# DJ_CONTROLLER.net
KiCad netlist of a schematic drawn in EAGLE
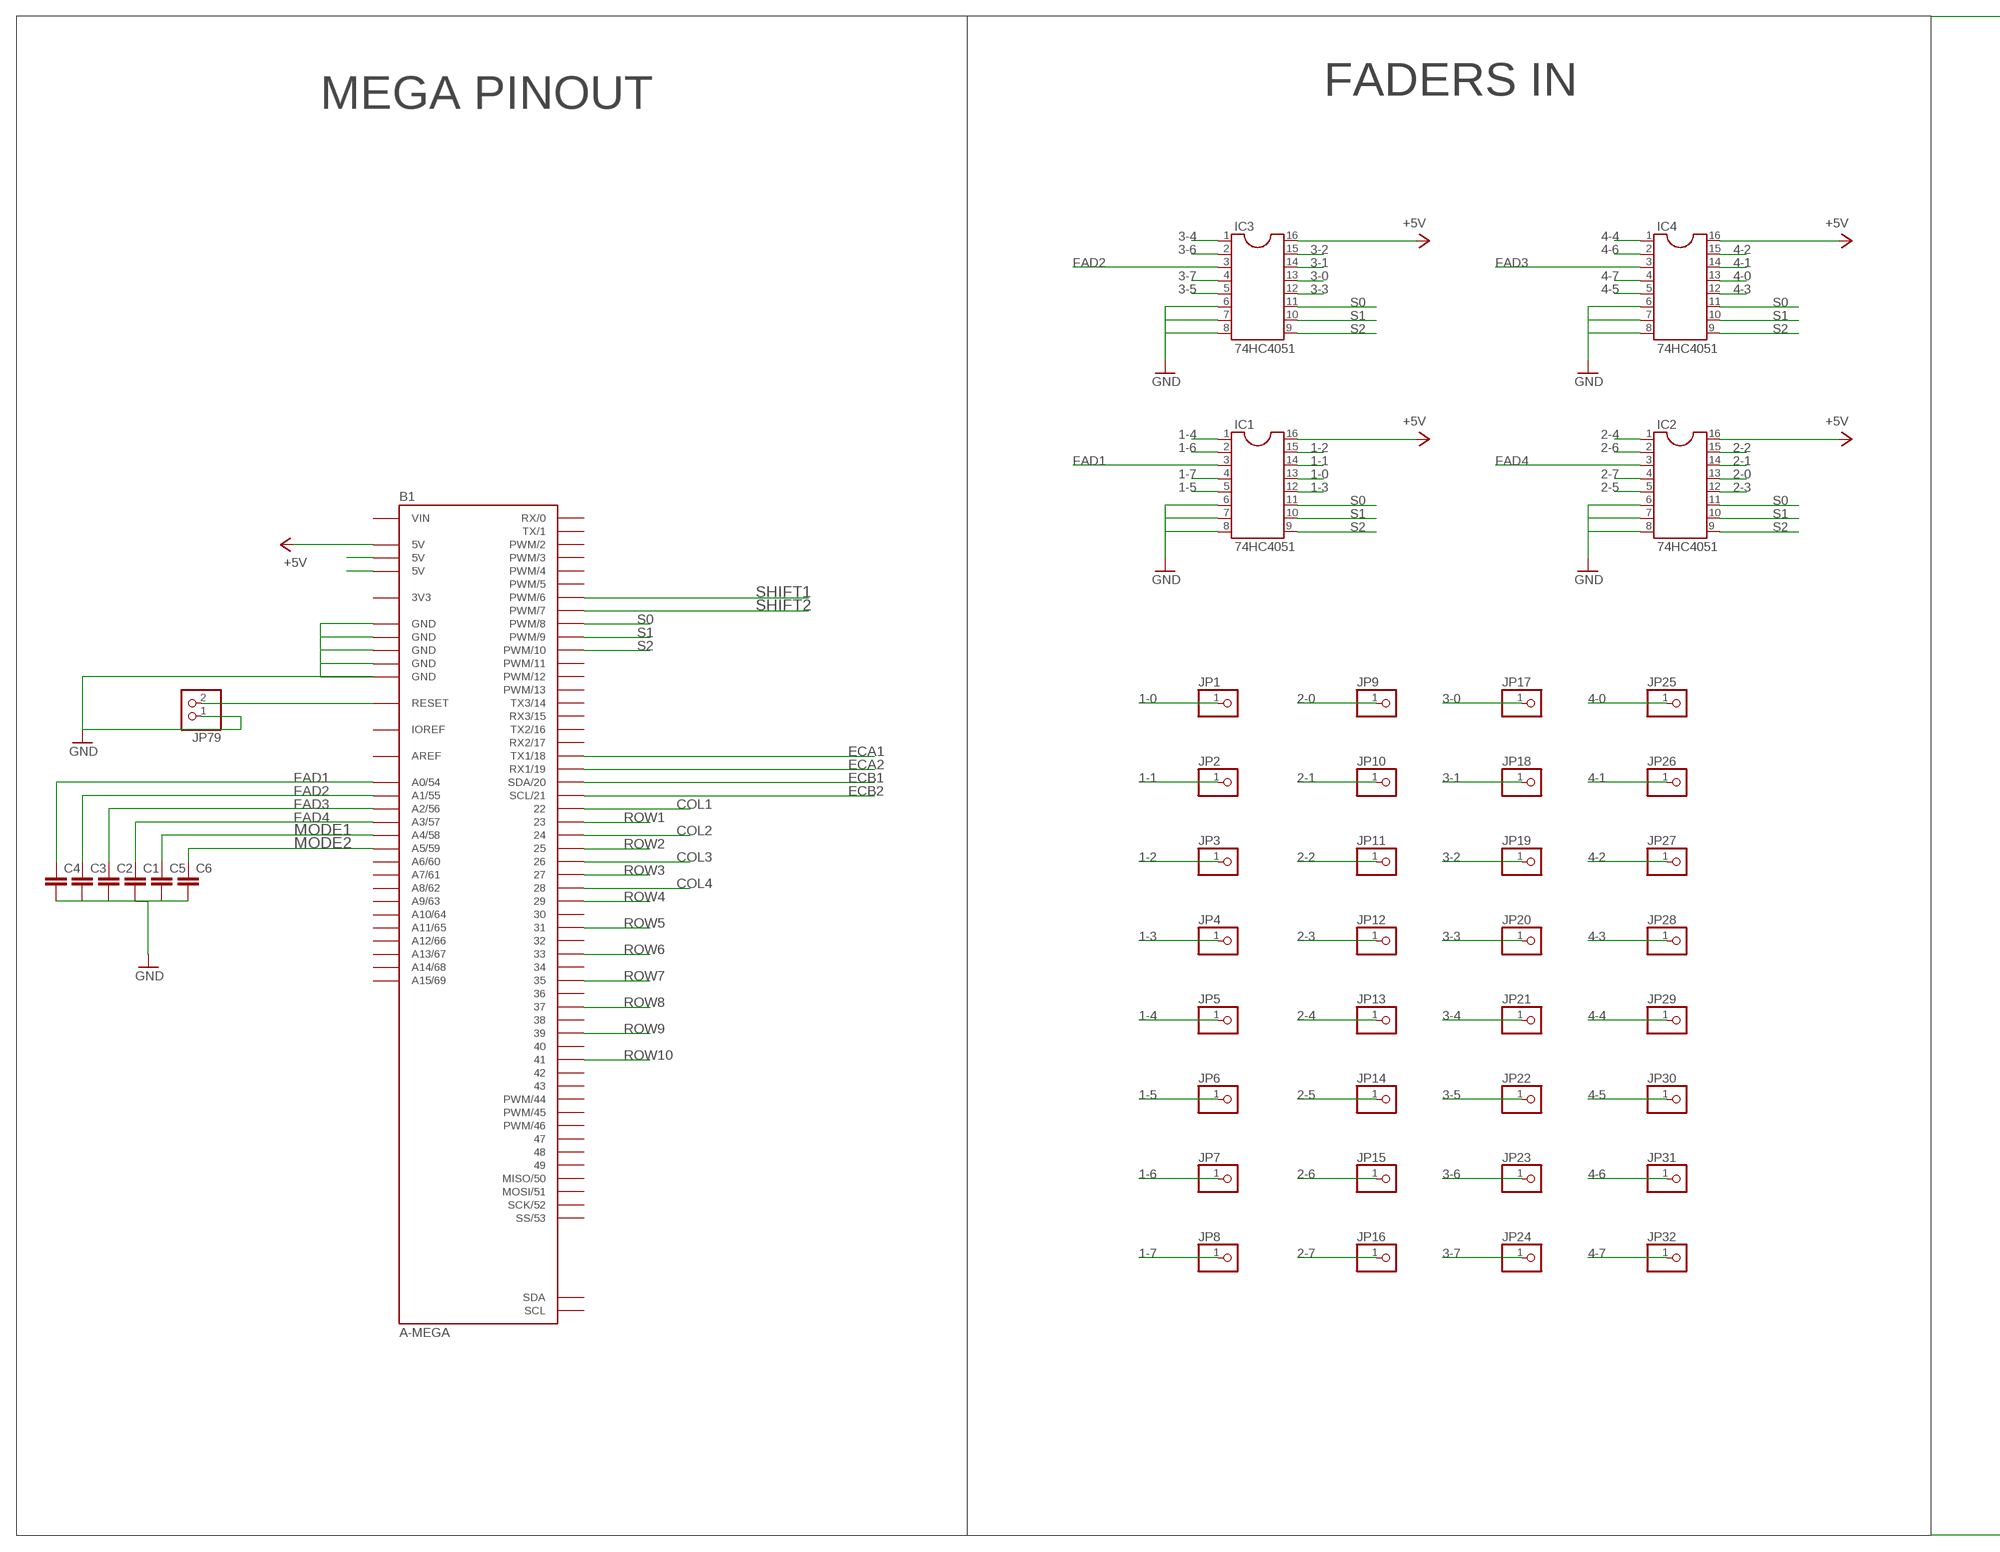
[diagram p0: schematic, sheet 1, part 1 of 2]
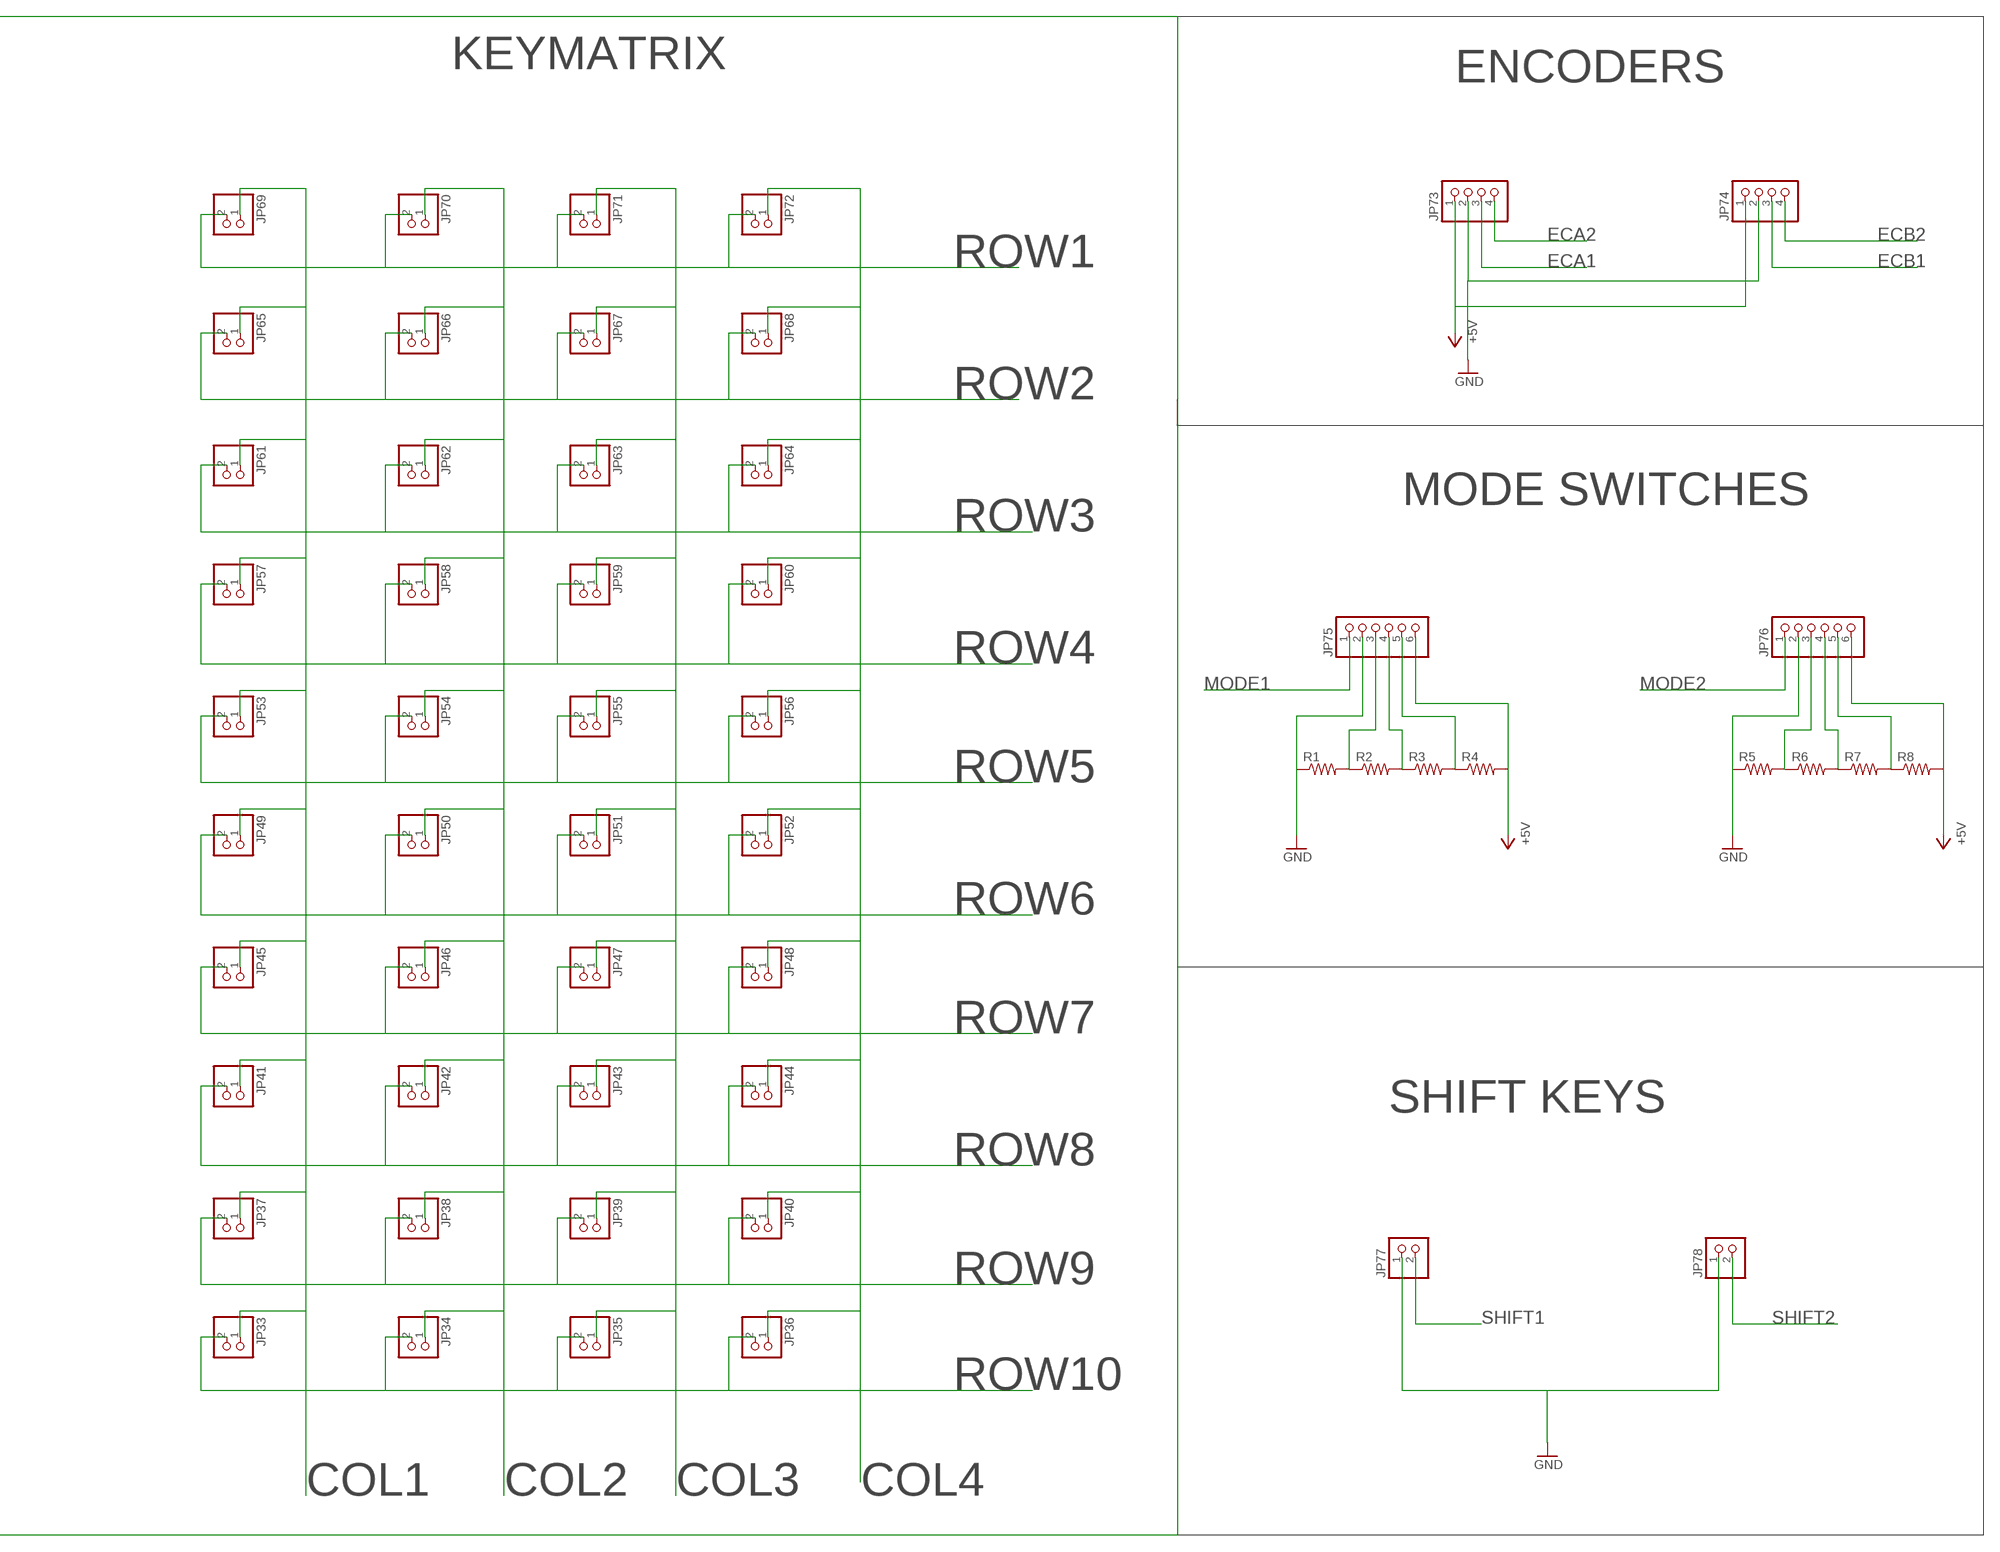
[diagram p1: schematic, sheet 1, part 2 of 2]

(export (version "E")
  (design (tool "Eeschema 10.0.6"))
  (components
    (comp (ref "B1")
      (value "A-MEGA")
      (footprint "eagle-import:A-MEGA")
      (libsource (lib "eagle-import") (part "A-MEGA"))
    )
    (comp (ref "C1")
      (value "C-EU050-025X075")
      (footprint "eagle-import:C050-025X075")
      (libsource (lib "eagle-import") (part "C-EU050-025X075"))
    )
    (comp (ref "C2")
      (value "C-EU050-025X075")
      (footprint "eagle-import:C050-025X075")
      (libsource (lib "eagle-import") (part "C-EU050-025X075"))
    )
    (comp (ref "C3")
      (value "C-EU050-025X075")
      (footprint "eagle-import:C050-025X075")
      (libsource (lib "eagle-import") (part "C-EU050-025X075"))
    )
    (comp (ref "C4")
      (value "C-EU050-025X075")
      (footprint "eagle-import:C050-025X075")
      (libsource (lib "eagle-import") (part "C-EU050-025X075"))
    )
    (comp (ref "C5")
      (value "C-EU050-025X075")
      (footprint "eagle-import:C050-025X075")
      (libsource (lib "eagle-import") (part "C-EU050-025X075"))
    )
    (comp (ref "C6")
      (value "C-EU050-025X075")
      (footprint "eagle-import:C050-025X075")
      (libsource (lib "eagle-import") (part "C-EU050-025X075"))
    )
    (comp (ref "IC1")
      (value "74HC4051")
      (footprint "eagle-import:SOCKET-16")
      (libsource (lib "eagle-import") (part "DIL16S"))
    )
    (comp (ref "IC2")
      (value "74HC4051")
      (footprint "eagle-import:SOCKET-16")
      (libsource (lib "eagle-import") (part "DIL16S"))
    )
    (comp (ref "IC3")
      (value "74HC4051")
      (footprint "eagle-import:SOCKET-16")
      (libsource (lib "eagle-import") (part "DIL16S"))
    )
    (comp (ref "IC4")
      (value "74HC4051")
      (footprint "eagle-import:SOCKET-16")
      (libsource (lib "eagle-import") (part "DIL16S"))
    )
    (comp (ref "JP1")
      (value "PINHD-1X1")
      (footprint "eagle-import:1X01")
      (libsource (lib "eagle-import") (part "PINHD-1X1"))
    )
    (comp (ref "JP2")
      (value "PINHD-1X1")
      (footprint "eagle-import:1X01")
      (libsource (lib "eagle-import") (part "PINHD-1X1"))
    )
    (comp (ref "JP3")
      (value "PINHD-1X1")
      (footprint "eagle-import:1X01")
      (libsource (lib "eagle-import") (part "PINHD-1X1"))
    )
    (comp (ref "JP4")
      (value "PINHD-1X1")
      (footprint "eagle-import:1X01")
      (libsource (lib "eagle-import") (part "PINHD-1X1"))
    )
    (comp (ref "JP5")
      (value "PINHD-1X1")
      (footprint "eagle-import:1X01")
      (libsource (lib "eagle-import") (part "PINHD-1X1"))
    )
    (comp (ref "JP6")
      (value "PINHD-1X1")
      (footprint "eagle-import:1X01")
      (libsource (lib "eagle-import") (part "PINHD-1X1"))
    )
    (comp (ref "JP7")
      (value "PINHD-1X1")
      (footprint "eagle-import:1X01")
      (libsource (lib "eagle-import") (part "PINHD-1X1"))
    )
    (comp (ref "JP8")
      (value "PINHD-1X1")
      (footprint "eagle-import:1X01")
      (libsource (lib "eagle-import") (part "PINHD-1X1"))
    )
    (comp (ref "JP9")
      (value "PINHD-1X1")
      (footprint "eagle-import:1X01")
      (libsource (lib "eagle-import") (part "PINHD-1X1"))
    )
    (comp (ref "JP10")
      (value "PINHD-1X1")
      (footprint "eagle-import:1X01")
      (libsource (lib "eagle-import") (part "PINHD-1X1"))
    )
    (comp (ref "JP11")
      (value "PINHD-1X1")
      (footprint "eagle-import:1X01")
      (libsource (lib "eagle-import") (part "PINHD-1X1"))
    )
    (comp (ref "JP12")
      (value "PINHD-1X1")
      (footprint "eagle-import:1X01")
      (libsource (lib "eagle-import") (part "PINHD-1X1"))
    )
    (comp (ref "JP13")
      (value "PINHD-1X1")
      (footprint "eagle-import:1X01")
      (libsource (lib "eagle-import") (part "PINHD-1X1"))
    )
    (comp (ref "JP14")
      (value "PINHD-1X1")
      (footprint "eagle-import:1X01")
      (libsource (lib "eagle-import") (part "PINHD-1X1"))
    )
    (comp (ref "JP15")
      (value "PINHD-1X1")
      (footprint "eagle-import:1X01")
      (libsource (lib "eagle-import") (part "PINHD-1X1"))
    )
    (comp (ref "JP16")
      (value "PINHD-1X1")
      (footprint "eagle-import:1X01")
      (libsource (lib "eagle-import") (part "PINHD-1X1"))
    )
    (comp (ref "JP17")
      (value "PINHD-1X1")
      (footprint "eagle-import:1X01")
      (libsource (lib "eagle-import") (part "PINHD-1X1"))
    )
    (comp (ref "JP18")
      (value "PINHD-1X1")
      (footprint "eagle-import:1X01")
      (libsource (lib "eagle-import") (part "PINHD-1X1"))
    )
    (comp (ref "JP19")
      (value "PINHD-1X1")
      (footprint "eagle-import:1X01")
      (libsource (lib "eagle-import") (part "PINHD-1X1"))
    )
    (comp (ref "JP20")
      (value "PINHD-1X1")
      (footprint "eagle-import:1X01")
      (libsource (lib "eagle-import") (part "PINHD-1X1"))
    )
    (comp (ref "JP21")
      (value "PINHD-1X1")
      (footprint "eagle-import:1X01")
      (libsource (lib "eagle-import") (part "PINHD-1X1"))
    )
    (comp (ref "JP22")
      (value "PINHD-1X1")
      (footprint "eagle-import:1X01")
      (libsource (lib "eagle-import") (part "PINHD-1X1"))
    )
    (comp (ref "JP23")
      (value "PINHD-1X1")
      (footprint "eagle-import:1X01")
      (libsource (lib "eagle-import") (part "PINHD-1X1"))
    )
    (comp (ref "JP24")
      (value "PINHD-1X1")
      (footprint "eagle-import:1X01")
      (libsource (lib "eagle-import") (part "PINHD-1X1"))
    )
    (comp (ref "JP25")
      (value "PINHD-1X1")
      (footprint "eagle-import:1X01")
      (libsource (lib "eagle-import") (part "PINHD-1X1"))
    )
    (comp (ref "JP26")
      (value "PINHD-1X1")
      (footprint "eagle-import:1X01")
      (libsource (lib "eagle-import") (part "PINHD-1X1"))
    )
    (comp (ref "JP27")
      (value "PINHD-1X1")
      (footprint "eagle-import:1X01")
      (libsource (lib "eagle-import") (part "PINHD-1X1"))
    )
    (comp (ref "JP28")
      (value "PINHD-1X1")
      (footprint "eagle-import:1X01")
      (libsource (lib "eagle-import") (part "PINHD-1X1"))
    )
    (comp (ref "JP29")
      (value "PINHD-1X1")
      (footprint "eagle-import:1X01")
      (libsource (lib "eagle-import") (part "PINHD-1X1"))
    )
    (comp (ref "JP30")
      (value "PINHD-1X1")
      (footprint "eagle-import:1X01")
      (libsource (lib "eagle-import") (part "PINHD-1X1"))
    )
    (comp (ref "JP31")
      (value "PINHD-1X1")
      (footprint "eagle-import:1X01")
      (libsource (lib "eagle-import") (part "PINHD-1X1"))
    )
    (comp (ref "JP32")
      (value "PINHD-1X1")
      (footprint "eagle-import:1X01")
      (libsource (lib "eagle-import") (part "PINHD-1X1"))
    )
    (comp (ref "JP33")
      (value "PINHD-1X2")
      (footprint "eagle-import:1X02")
      (libsource (lib "eagle-import") (part "PINHD-1X2"))
    )
    (comp (ref "JP34")
      (value "PINHD-1X2")
      (footprint "eagle-import:1X02")
      (libsource (lib "eagle-import") (part "PINHD-1X2"))
    )
    (comp (ref "JP35")
      (value "PINHD-1X2")
      (footprint "eagle-import:1X02")
      (libsource (lib "eagle-import") (part "PINHD-1X2"))
    )
    (comp (ref "JP36")
      (value "PINHD-1X2")
      (footprint "eagle-import:1X02")
      (libsource (lib "eagle-import") (part "PINHD-1X2"))
    )
    (comp (ref "JP37")
      (value "PINHD-1X2")
      (footprint "eagle-import:1X02")
      (libsource (lib "eagle-import") (part "PINHD-1X2"))
    )
    (comp (ref "JP38")
      (value "PINHD-1X2")
      (footprint "eagle-import:1X02")
      (libsource (lib "eagle-import") (part "PINHD-1X2"))
    )
    (comp (ref "JP39")
      (value "PINHD-1X2")
      (footprint "eagle-import:1X02")
      (libsource (lib "eagle-import") (part "PINHD-1X2"))
    )
    (comp (ref "JP40")
      (value "PINHD-1X2")
      (footprint "eagle-import:1X02")
      (libsource (lib "eagle-import") (part "PINHD-1X2"))
    )
    (comp (ref "JP41")
      (value "PINHD-1X2")
      (footprint "eagle-import:1X02")
      (libsource (lib "eagle-import") (part "PINHD-1X2"))
    )
    (comp (ref "JP42")
      (value "PINHD-1X2")
      (footprint "eagle-import:1X02")
      (libsource (lib "eagle-import") (part "PINHD-1X2"))
    )
    (comp (ref "JP43")
      (value "PINHD-1X2")
      (footprint "eagle-import:1X02")
      (libsource (lib "eagle-import") (part "PINHD-1X2"))
    )
    (comp (ref "JP44")
      (value "PINHD-1X2")
      (footprint "eagle-import:1X02")
      (libsource (lib "eagle-import") (part "PINHD-1X2"))
    )
    (comp (ref "JP45")
      (value "PINHD-1X2")
      (footprint "eagle-import:1X02")
      (libsource (lib "eagle-import") (part "PINHD-1X2"))
    )
    (comp (ref "JP46")
      (value "PINHD-1X2")
      (footprint "eagle-import:1X02")
      (libsource (lib "eagle-import") (part "PINHD-1X2"))
    )
    (comp (ref "JP47")
      (value "PINHD-1X2")
      (footprint "eagle-import:1X02")
      (libsource (lib "eagle-import") (part "PINHD-1X2"))
    )
    (comp (ref "JP48")
      (value "PINHD-1X2")
      (footprint "eagle-import:1X02")
      (libsource (lib "eagle-import") (part "PINHD-1X2"))
    )
    (comp (ref "JP49")
      (value "PINHD-1X2")
      (footprint "eagle-import:1X02")
      (libsource (lib "eagle-import") (part "PINHD-1X2"))
    )
    (comp (ref "JP50")
      (value "PINHD-1X2")
      (footprint "eagle-import:1X02")
      (libsource (lib "eagle-import") (part "PINHD-1X2"))
    )
    (comp (ref "JP51")
      (value "PINHD-1X2")
      (footprint "eagle-import:1X02")
      (libsource (lib "eagle-import") (part "PINHD-1X2"))
    )
    (comp (ref "JP52")
      (value "PINHD-1X2")
      (footprint "eagle-import:1X02")
      (libsource (lib "eagle-import") (part "PINHD-1X2"))
    )
    (comp (ref "JP53")
      (value "PINHD-1X2")
      (footprint "eagle-import:1X02")
      (libsource (lib "eagle-import") (part "PINHD-1X2"))
    )
    (comp (ref "JP54")
      (value "PINHD-1X2")
      (footprint "eagle-import:1X02")
      (libsource (lib "eagle-import") (part "PINHD-1X2"))
    )
    (comp (ref "JP55")
      (value "PINHD-1X2")
      (footprint "eagle-import:1X02")
      (libsource (lib "eagle-import") (part "PINHD-1X2"))
    )
    (comp (ref "JP56")
      (value "PINHD-1X2")
      (footprint "eagle-import:1X02")
      (libsource (lib "eagle-import") (part "PINHD-1X2"))
    )
    (comp (ref "JP57")
      (value "PINHD-1X2")
      (footprint "eagle-import:1X02")
      (libsource (lib "eagle-import") (part "PINHD-1X2"))
    )
    (comp (ref "JP58")
      (value "PINHD-1X2")
      (footprint "eagle-import:1X02")
      (libsource (lib "eagle-import") (part "PINHD-1X2"))
    )
    (comp (ref "JP59")
      (value "PINHD-1X2")
      (footprint "eagle-import:1X02")
      (libsource (lib "eagle-import") (part "PINHD-1X2"))
    )
    (comp (ref "JP60")
      (value "PINHD-1X2")
      (footprint "eagle-import:1X02")
      (libsource (lib "eagle-import") (part "PINHD-1X2"))
    )
    (comp (ref "JP61")
      (value "PINHD-1X2")
      (footprint "eagle-import:1X02")
      (libsource (lib "eagle-import") (part "PINHD-1X2"))
    )
    (comp (ref "JP62")
      (value "PINHD-1X2")
      (footprint "eagle-import:1X02")
      (libsource (lib "eagle-import") (part "PINHD-1X2"))
    )
    (comp (ref "JP63")
      (value "PINHD-1X2")
      (footprint "eagle-import:1X02")
      (libsource (lib "eagle-import") (part "PINHD-1X2"))
    )
    (comp (ref "JP64")
      (value "PINHD-1X2")
      (footprint "eagle-import:1X02")
      (libsource (lib "eagle-import") (part "PINHD-1X2"))
    )
    (comp (ref "JP65")
      (value "PINHD-1X2")
      (footprint "eagle-import:1X02")
      (libsource (lib "eagle-import") (part "PINHD-1X2"))
    )
    (comp (ref "JP66")
      (value "PINHD-1X2")
      (footprint "eagle-import:1X02")
      (libsource (lib "eagle-import") (part "PINHD-1X2"))
    )
    (comp (ref "JP67")
      (value "PINHD-1X2")
      (footprint "eagle-import:1X02")
      (libsource (lib "eagle-import") (part "PINHD-1X2"))
    )
    (comp (ref "JP68")
      (value "PINHD-1X2")
      (footprint "eagle-import:1X02")
      (libsource (lib "eagle-import") (part "PINHD-1X2"))
    )
    (comp (ref "JP69")
      (value "PINHD-1X2")
      (footprint "eagle-import:1X02")
      (libsource (lib "eagle-import") (part "PINHD-1X2"))
    )
    (comp (ref "JP70")
      (value "PINHD-1X2")
      (footprint "eagle-import:1X02")
      (libsource (lib "eagle-import") (part "PINHD-1X2"))
    )
    (comp (ref "JP71")
      (value "PINHD-1X2")
      (footprint "eagle-import:1X02")
      (libsource (lib "eagle-import") (part "PINHD-1X2"))
    )
    (comp (ref "JP72")
      (value "PINHD-1X2")
      (footprint "eagle-import:1X02")
      (libsource (lib "eagle-import") (part "PINHD-1X2"))
    )
    (comp (ref "JP73")
      (value "PINHD-1X4")
      (footprint "eagle-import:1X04")
      (libsource (lib "eagle-import") (part "PINHD-1X4"))
    )
    (comp (ref "JP74")
      (value "PINHD-1X4")
      (footprint "eagle-import:1X04")
      (libsource (lib "eagle-import") (part "PINHD-1X4"))
    )
    (comp (ref "JP75")
      (value "PINHD-1X6")
      (footprint "eagle-import:1X06")
      (libsource (lib "eagle-import") (part "PINHD-1X6"))
    )
    (comp (ref "JP76")
      (value "PINHD-1X6")
      (footprint "eagle-import:1X06")
      (libsource (lib "eagle-import") (part "PINHD-1X6"))
    )
    (comp (ref "JP77")
      (value "PINHD-1X2")
      (footprint "eagle-import:1X02")
      (libsource (lib "eagle-import") (part "PINHD-1X2"))
    )
    (comp (ref "JP78")
      (value "PINHD-1X2")
      (footprint "eagle-import:1X02")
      (libsource (lib "eagle-import") (part "PINHD-1X2"))
    )
    (comp (ref "JP79")
      (value "PINHD-1X2")
      (footprint "eagle-import:1X02")
      (libsource (lib "eagle-import") (part "PINHD-1X2"))
    )
    (comp (ref "R1")
      (value "R-US_0204/7")
      (footprint "eagle-import:0204_7")
      (libsource (lib "eagle-import") (part "R-US_0204/7"))
    )
    (comp (ref "R2")
      (value "R-US_0204/7")
      (footprint "eagle-import:0204_7")
      (libsource (lib "eagle-import") (part "R-US_0204/7"))
    )
    (comp (ref "R3")
      (value "R-US_0204/7")
      (footprint "eagle-import:0204_7")
      (libsource (lib "eagle-import") (part "R-US_0204/7"))
    )
    (comp (ref "R4")
      (value "R-US_0204/7")
      (footprint "eagle-import:0204_7")
      (libsource (lib "eagle-import") (part "R-US_0204/7"))
    )
    (comp (ref "R5")
      (value "R-US_0204/7")
      (footprint "eagle-import:0204_7")
      (libsource (lib "eagle-import") (part "R-US_0204/7"))
    )
    (comp (ref "R6")
      (value "R-US_0204/7")
      (footprint "eagle-import:0204_7")
      (libsource (lib "eagle-import") (part "R-US_0204/7"))
    )
    (comp (ref "R7")
      (value "R-US_0204/7")
      (footprint "eagle-import:0204_7")
      (libsource (lib "eagle-import") (part "R-US_0204/7"))
    )
    (comp (ref "R8")
      (value "R-US_0204/7")
      (footprint "eagle-import:0204_7")
      (libsource (lib "eagle-import") (part "R-US_0204/7"))
    )
  )
  (nets
    (net (code "1") (name "+5V") (class "Default")
      (node (ref "B1") (pin "5V@1") (pinfunction "5V_5V@1") (pintype "power_in"))
      (node (ref "IC1") (pin "16") (pinfunction "16_16") (pintype "passive"))
      (node (ref "IC2") (pin "16") (pinfunction "16_16") (pintype "passive"))
      (node (ref "IC3") (pin "16") (pinfunction "16_16") (pintype "passive"))
      (node (ref "IC4") (pin "16") (pinfunction "16_16") (pintype "passive"))
      (node (ref "JP73") (pin "1") (pinfunction "1_1") (pintype "passive"))
      (node (ref "JP74") (pin "1") (pinfunction "1_1") (pintype "passive"))
      (node (ref "JP75") (pin "6") (pinfunction "6_6") (pintype "passive"))
      (node (ref "JP76") (pin "6") (pinfunction "6_6") (pintype "passive"))
      (node (ref "R4") (pin "2") (pinfunction "2_2") (pintype "passive"))
      (node (ref "R8") (pin "2") (pinfunction "2_2") (pintype "passive"))
    )
    (net (code "2") (name "/1-0") (class "Default")
      (node (ref "IC1") (pin "13") (pinfunction "13_13") (pintype "passive"))
      (node (ref "JP1") (pin "1") (pinfunction "1_1") (pintype "passive"))
    )
    (net (code "3") (name "/1-1") (class "Default")
      (node (ref "IC1") (pin "14") (pinfunction "14_14") (pintype "passive"))
      (node (ref "JP2") (pin "1") (pinfunction "1_1") (pintype "passive"))
    )
    (net (code "4") (name "/1-2") (class "Default")
      (node (ref "IC1") (pin "15") (pinfunction "15_15") (pintype "passive"))
      (node (ref "JP3") (pin "1") (pinfunction "1_1") (pintype "passive"))
    )
    (net (code "5") (name "/1-3") (class "Default")
      (node (ref "IC1") (pin "12") (pinfunction "12_12") (pintype "passive"))
      (node (ref "JP4") (pin "1") (pinfunction "1_1") (pintype "passive"))
    )
    (net (code "6") (name "/1-4") (class "Default")
      (node (ref "IC1") (pin "1") (pinfunction "1_1") (pintype "passive"))
      (node (ref "JP5") (pin "1") (pinfunction "1_1") (pintype "passive"))
    )
    (net (code "7") (name "/1-5") (class "Default")
      (node (ref "IC1") (pin "5") (pinfunction "5_5") (pintype "passive"))
      (node (ref "JP6") (pin "1") (pinfunction "1_1") (pintype "passive"))
    )
    (net (code "8") (name "/1-6") (class "Default")
      (node (ref "IC1") (pin "2") (pinfunction "2_2") (pintype "passive"))
      (node (ref "JP7") (pin "1") (pinfunction "1_1") (pintype "passive"))
    )
    (net (code "9") (name "/1-7") (class "Default")
      (node (ref "IC1") (pin "4") (pinfunction "4_4") (pintype "passive"))
      (node (ref "JP8") (pin "1") (pinfunction "1_1") (pintype "passive"))
    )
    (net (code "10") (name "/2-0") (class "Default")
      (node (ref "IC2") (pin "13") (pinfunction "13_13") (pintype "passive"))
      (node (ref "JP9") (pin "1") (pinfunction "1_1") (pintype "passive"))
    )
    (net (code "11") (name "/2-1") (class "Default")
      (node (ref "IC2") (pin "14") (pinfunction "14_14") (pintype "passive"))
      (node (ref "JP10") (pin "1") (pinfunction "1_1") (pintype "passive"))
    )
    (net (code "12") (name "/2-2") (class "Default")
      (node (ref "IC2") (pin "15") (pinfunction "15_15") (pintype "passive"))
      (node (ref "JP11") (pin "1") (pinfunction "1_1") (pintype "passive"))
    )
    (net (code "13") (name "/2-3") (class "Default")
      (node (ref "IC2") (pin "12") (pinfunction "12_12") (pintype "passive"))
      (node (ref "JP12") (pin "1") (pinfunction "1_1") (pintype "passive"))
    )
    (net (code "14") (name "/2-4") (class "Default")
      (node (ref "IC2") (pin "1") (pinfunction "1_1") (pintype "passive"))
      (node (ref "JP13") (pin "1") (pinfunction "1_1") (pintype "passive"))
    )
    (net (code "15") (name "/2-5") (class "Default")
      (node (ref "IC2") (pin "5") (pinfunction "5_5") (pintype "passive"))
      (node (ref "JP14") (pin "1") (pinfunction "1_1") (pintype "passive"))
    )
    (net (code "16") (name "/2-6") (class "Default")
      (node (ref "IC2") (pin "2") (pinfunction "2_2") (pintype "passive"))
      (node (ref "JP15") (pin "1") (pinfunction "1_1") (pintype "passive"))
    )
    (net (code "17") (name "/2-7") (class "Default")
      (node (ref "IC2") (pin "4") (pinfunction "4_4") (pintype "passive"))
      (node (ref "JP16") (pin "1") (pinfunction "1_1") (pintype "passive"))
    )
    (net (code "18") (name "/3-0") (class "Default")
      (node (ref "IC3") (pin "13") (pinfunction "13_13") (pintype "passive"))
      (node (ref "JP17") (pin "1") (pinfunction "1_1") (pintype "passive"))
    )
    (net (code "19") (name "/3-1") (class "Default")
      (node (ref "IC3") (pin "14") (pinfunction "14_14") (pintype "passive"))
      (node (ref "JP18") (pin "1") (pinfunction "1_1") (pintype "passive"))
    )
    (net (code "20") (name "/3-2") (class "Default")
      (node (ref "IC3") (pin "15") (pinfunction "15_15") (pintype "passive"))
      (node (ref "JP19") (pin "1") (pinfunction "1_1") (pintype "passive"))
    )
    (net (code "21") (name "/3-3") (class "Default")
      (node (ref "IC3") (pin "12") (pinfunction "12_12") (pintype "passive"))
      (node (ref "JP20") (pin "1") (pinfunction "1_1") (pintype "passive"))
    )
    (net (code "22") (name "/3-4") (class "Default")
      (node (ref "IC3") (pin "1") (pinfunction "1_1") (pintype "passive"))
      (node (ref "JP21") (pin "1") (pinfunction "1_1") (pintype "passive"))
    )
    (net (code "23") (name "/3-5") (class "Default")
      (node (ref "IC3") (pin "5") (pinfunction "5_5") (pintype "passive"))
      (node (ref "JP22") (pin "1") (pinfunction "1_1") (pintype "passive"))
    )
    (net (code "24") (name "/3-6") (class "Default")
      (node (ref "IC3") (pin "2") (pinfunction "2_2") (pintype "passive"))
      (node (ref "JP23") (pin "1") (pinfunction "1_1") (pintype "passive"))
    )
    (net (code "25") (name "/3-7") (class "Default")
      (node (ref "IC3") (pin "4") (pinfunction "4_4") (pintype "passive"))
      (node (ref "JP24") (pin "1") (pinfunction "1_1") (pintype "passive"))
    )
    (net (code "26") (name "/3V3") (class "Default")
      (node (ref "B1") (pin "3V3") (pinfunction "3V3_3V3") (pintype "power_in"))
    )
    (net (code "27") (name "/4-0") (class "Default")
      (node (ref "IC4") (pin "13") (pinfunction "13_13") (pintype "passive"))
      (node (ref "JP25") (pin "1") (pinfunction "1_1") (pintype "passive"))
    )
    (net (code "28") (name "/4-1") (class "Default")
      (node (ref "IC4") (pin "14") (pinfunction "14_14") (pintype "passive"))
      (node (ref "JP26") (pin "1") (pinfunction "1_1") (pintype "passive"))
    )
    (net (code "29") (name "/4-2") (class "Default")
      (node (ref "IC4") (pin "15") (pinfunction "15_15") (pintype "passive"))
      (node (ref "JP27") (pin "1") (pinfunction "1_1") (pintype "passive"))
    )
    (net (code "30") (name "/4-3") (class "Default")
      (node (ref "IC4") (pin "12") (pinfunction "12_12") (pintype "passive"))
      (node (ref "JP28") (pin "1") (pinfunction "1_1") (pintype "passive"))
    )
    (net (code "31") (name "/4-4") (class "Default")
      (node (ref "IC4") (pin "1") (pinfunction "1_1") (pintype "passive"))
      (node (ref "JP29") (pin "1") (pinfunction "1_1") (pintype "passive"))
    )
    (net (code "32") (name "/4-5") (class "Default")
      (node (ref "IC4") (pin "5") (pinfunction "5_5") (pintype "passive"))
      (node (ref "JP30") (pin "1") (pinfunction "1_1") (pintype "passive"))
    )
    (net (code "33") (name "/4-6") (class "Default")
      (node (ref "IC4") (pin "2") (pinfunction "2_2") (pintype "passive"))
      (node (ref "JP31") (pin "1") (pinfunction "1_1") (pintype "passive"))
    )
    (net (code "34") (name "/4-7") (class "Default")
      (node (ref "IC4") (pin "4") (pinfunction "4_4") (pintype "passive"))
      (node (ref "JP32") (pin "1") (pinfunction "1_1") (pintype "passive"))
    )
    (net (code "35") (name "/AREF") (class "Default")
      (node (ref "B1") (pin "AREF") (pinfunction "AREF_AREF") (pintype "power_in"))
    )
    (net (code "36") (name "/COL1") (class "Default")
      (node (ref "B1") (pin "22") (pinfunction "22_22") (pintype "bidirectional"))
      (node (ref "JP33") (pin "1") (pinfunction "1_1") (pintype "passive"))
      (node (ref "JP37") (pin "1") (pinfunction "1_1") (pintype "passive"))
      (node (ref "JP41") (pin "1") (pinfunction "1_1") (pintype "passive"))
      (node (ref "JP45") (pin "1") (pinfunction "1_1") (pintype "passive"))
      (node (ref "JP49") (pin "1") (pinfunction "1_1") (pintype "passive"))
      (node (ref "JP53") (pin "1") (pinfunction "1_1") (pintype "passive"))
      (node (ref "JP57") (pin "1") (pinfunction "1_1") (pintype "passive"))
      (node (ref "JP61") (pin "1") (pinfunction "1_1") (pintype "passive"))
      (node (ref "JP65") (pin "1") (pinfunction "1_1") (pintype "passive"))
      (node (ref "JP69") (pin "1") (pinfunction "1_1") (pintype "passive"))
    )
    (net (code "37") (name "/COL2") (class "Default")
      (node (ref "B1") (pin "24") (pinfunction "24_24") (pintype "bidirectional"))
      (node (ref "JP34") (pin "1") (pinfunction "1_1") (pintype "passive"))
      (node (ref "JP38") (pin "1") (pinfunction "1_1") (pintype "passive"))
      (node (ref "JP42") (pin "1") (pinfunction "1_1") (pintype "passive"))
      (node (ref "JP46") (pin "1") (pinfunction "1_1") (pintype "passive"))
      (node (ref "JP50") (pin "1") (pinfunction "1_1") (pintype "passive"))
      (node (ref "JP54") (pin "1") (pinfunction "1_1") (pintype "passive"))
      (node (ref "JP58") (pin "1") (pinfunction "1_1") (pintype "passive"))
      (node (ref "JP62") (pin "1") (pinfunction "1_1") (pintype "passive"))
      (node (ref "JP66") (pin "1") (pinfunction "1_1") (pintype "passive"))
      (node (ref "JP70") (pin "1") (pinfunction "1_1") (pintype "passive"))
    )
    (net (code "38") (name "/COL3") (class "Default")
      (node (ref "B1") (pin "26") (pinfunction "26_26") (pintype "bidirectional"))
      (node (ref "JP35") (pin "1") (pinfunction "1_1") (pintype "passive"))
      (node (ref "JP39") (pin "1") (pinfunction "1_1") (pintype "passive"))
      (node (ref "JP43") (pin "1") (pinfunction "1_1") (pintype "passive"))
      (node (ref "JP47") (pin "1") (pinfunction "1_1") (pintype "passive"))
      (node (ref "JP51") (pin "1") (pinfunction "1_1") (pintype "passive"))
      (node (ref "JP55") (pin "1") (pinfunction "1_1") (pintype "passive"))
      (node (ref "JP59") (pin "1") (pinfunction "1_1") (pintype "passive"))
      (node (ref "JP63") (pin "1") (pinfunction "1_1") (pintype "passive"))
      (node (ref "JP67") (pin "1") (pinfunction "1_1") (pintype "passive"))
      (node (ref "JP71") (pin "1") (pinfunction "1_1") (pintype "passive"))
    )
    (net (code "39") (name "/COL4") (class "Default")
      (node (ref "B1") (pin "28") (pinfunction "28_28") (pintype "bidirectional"))
      (node (ref "JP36") (pin "1") (pinfunction "1_1") (pintype "passive"))
      (node (ref "JP40") (pin "1") (pinfunction "1_1") (pintype "passive"))
      (node (ref "JP44") (pin "1") (pinfunction "1_1") (pintype "passive"))
      (node (ref "JP48") (pin "1") (pinfunction "1_1") (pintype "passive"))
      (node (ref "JP52") (pin "1") (pinfunction "1_1") (pintype "passive"))
      (node (ref "JP56") (pin "1") (pinfunction "1_1") (pintype "passive"))
      (node (ref "JP60") (pin "1") (pinfunction "1_1") (pintype "passive"))
      (node (ref "JP64") (pin "1") (pinfunction "1_1") (pintype "passive"))
      (node (ref "JP68") (pin "1") (pinfunction "1_1") (pintype "passive"))
      (node (ref "JP72") (pin "1") (pinfunction "1_1") (pintype "passive"))
    )
    (net (code "40") (name "/ECA1") (class "Default")
      (node (ref "B1") (pin "18") (pinfunction "TX1/18_18") (pintype "bidirectional"))
      (node (ref "JP73") (pin "3") (pinfunction "3_3") (pintype "passive"))
    )
    (net (code "41") (name "/ECA2") (class "Default")
      (node (ref "B1") (pin "19") (pinfunction "RX1/19_19") (pintype "bidirectional"))
      (node (ref "JP73") (pin "4") (pinfunction "4_4") (pintype "passive"))
    )
    (net (code "42") (name "/ECB1") (class "Default")
      (node (ref "B1") (pin "20") (pinfunction "SDA/20_20") (pintype "bidirectional"))
      (node (ref "JP74") (pin "3") (pinfunction "3_3") (pintype "passive"))
    )
    (net (code "43") (name "/ECB2") (class "Default")
      (node (ref "B1") (pin "21") (pinfunction "SCL/21_21") (pintype "bidirectional"))
      (node (ref "JP74") (pin "4") (pinfunction "4_4") (pintype "passive"))
    )
    (net (code "44") (name "/FAD1") (class "Default")
      (node (ref "B1") (pin "A0") (pinfunction "A0/54_A0") (pintype "bidirectional"))
      (node (ref "C4") (pin "1") (pinfunction "1_1") (pintype "passive"))
      (node (ref "IC1") (pin "3") (pinfunction "3_3") (pintype "passive"))
    )
    (net (code "45") (name "/FAD2") (class "Default")
      (node (ref "B1") (pin "A1") (pinfunction "A1/55_A1") (pintype "bidirectional"))
      (node (ref "C3") (pin "1") (pinfunction "1_1") (pintype "passive"))
      (node (ref "IC3") (pin "3") (pinfunction "3_3") (pintype "passive"))
    )
    (net (code "46") (name "/FAD3") (class "Default")
      (node (ref "B1") (pin "A2") (pinfunction "A2/56_A2") (pintype "bidirectional"))
      (node (ref "C2") (pin "1") (pinfunction "1_1") (pintype "passive"))
      (node (ref "IC4") (pin "3") (pinfunction "3_3") (pintype "passive"))
    )
    (net (code "47") (name "/FAD4") (class "Default")
      (node (ref "B1") (pin "A3") (pinfunction "A3/57_A3") (pintype "bidirectional"))
      (node (ref "C1") (pin "1") (pinfunction "1_1") (pintype "passive"))
      (node (ref "IC2") (pin "3") (pinfunction "3_3") (pintype "passive"))
    )
    (net (code "48") (name "/IOREF") (class "Default")
      (node (ref "B1") (pin "IOREF") (pinfunction "IOREF_IOREF") (pintype "power_in"))
    )
    (net (code "49") (name "/MODE1") (class "Default")
      (node (ref "B1") (pin "A4") (pinfunction "A4/58_A4") (pintype "bidirectional"))
      (node (ref "C5") (pin "1") (pinfunction "1_1") (pintype "passive"))
      (node (ref "JP75") (pin "1") (pinfunction "1_1") (pintype "passive"))
    )
    (net (code "50") (name "/MODE2") (class "Default")
      (node (ref "B1") (pin "A5") (pinfunction "A5/59_A5") (pintype "bidirectional"))
      (node (ref "C6") (pin "1") (pinfunction "1_1") (pintype "passive"))
      (node (ref "JP76") (pin "1") (pinfunction "1_1") (pintype "passive"))
    )
    (net (code "51") (name "/ROW1") (class "Default")
      (node (ref "B1") (pin "23") (pinfunction "23_23") (pintype "bidirectional"))
      (node (ref "JP69") (pin "2") (pinfunction "2_2") (pintype "passive"))
      (node (ref "JP70") (pin "2") (pinfunction "2_2") (pintype "passive"))
      (node (ref "JP71") (pin "2") (pinfunction "2_2") (pintype "passive"))
      (node (ref "JP72") (pin "2") (pinfunction "2_2") (pintype "passive"))
    )
    (net (code "52") (name "/ROW2") (class "Default")
      (node (ref "B1") (pin "25") (pinfunction "25_25") (pintype "bidirectional"))
      (node (ref "JP65") (pin "2") (pinfunction "2_2") (pintype "passive"))
      (node (ref "JP66") (pin "2") (pinfunction "2_2") (pintype "passive"))
      (node (ref "JP67") (pin "2") (pinfunction "2_2") (pintype "passive"))
      (node (ref "JP68") (pin "2") (pinfunction "2_2") (pintype "passive"))
    )
    (net (code "53") (name "/ROW3") (class "Default")
      (node (ref "B1") (pin "27") (pinfunction "27_27") (pintype "bidirectional"))
      (node (ref "JP61") (pin "2") (pinfunction "2_2") (pintype "passive"))
      (node (ref "JP62") (pin "2") (pinfunction "2_2") (pintype "passive"))
      (node (ref "JP63") (pin "2") (pinfunction "2_2") (pintype "passive"))
      (node (ref "JP64") (pin "2") (pinfunction "2_2") (pintype "passive"))
    )
    (net (code "54") (name "/ROW4") (class "Default")
      (node (ref "B1") (pin "29") (pinfunction "29_29") (pintype "bidirectional"))
      (node (ref "JP57") (pin "2") (pinfunction "2_2") (pintype "passive"))
      (node (ref "JP58") (pin "2") (pinfunction "2_2") (pintype "passive"))
      (node (ref "JP59") (pin "2") (pinfunction "2_2") (pintype "passive"))
      (node (ref "JP60") (pin "2") (pinfunction "2_2") (pintype "passive"))
    )
    (net (code "55") (name "/ROW5") (class "Default")
      (node (ref "B1") (pin "31") (pinfunction "31_31") (pintype "bidirectional"))
      (node (ref "JP53") (pin "2") (pinfunction "2_2") (pintype "passive"))
      (node (ref "JP54") (pin "2") (pinfunction "2_2") (pintype "passive"))
      (node (ref "JP55") (pin "2") (pinfunction "2_2") (pintype "passive"))
      (node (ref "JP56") (pin "2") (pinfunction "2_2") (pintype "passive"))
    )
    (net (code "56") (name "/ROW6") (class "Default")
      (node (ref "B1") (pin "33") (pinfunction "33_33") (pintype "bidirectional"))
      (node (ref "JP49") (pin "2") (pinfunction "2_2") (pintype "passive"))
      (node (ref "JP50") (pin "2") (pinfunction "2_2") (pintype "passive"))
      (node (ref "JP51") (pin "2") (pinfunction "2_2") (pintype "passive"))
      (node (ref "JP52") (pin "2") (pinfunction "2_2") (pintype "passive"))
    )
    (net (code "57") (name "/ROW7") (class "Default")
      (node (ref "B1") (pin "35") (pinfunction "35_35") (pintype "bidirectional"))
      (node (ref "JP45") (pin "2") (pinfunction "2_2") (pintype "passive"))
      (node (ref "JP46") (pin "2") (pinfunction "2_2") (pintype "passive"))
      (node (ref "JP47") (pin "2") (pinfunction "2_2") (pintype "passive"))
      (node (ref "JP48") (pin "2") (pinfunction "2_2") (pintype "passive"))
    )
    (net (code "58") (name "/ROW8") (class "Default")
      (node (ref "B1") (pin "37") (pinfunction "37_37") (pintype "bidirectional"))
      (node (ref "JP41") (pin "2") (pinfunction "2_2") (pintype "passive"))
      (node (ref "JP42") (pin "2") (pinfunction "2_2") (pintype "passive"))
      (node (ref "JP43") (pin "2") (pinfunction "2_2") (pintype "passive"))
      (node (ref "JP44") (pin "2") (pinfunction "2_2") (pintype "passive"))
    )
    (net (code "59") (name "/ROW9") (class "Default")
      (node (ref "B1") (pin "39") (pinfunction "39_39") (pintype "bidirectional"))
      (node (ref "JP37") (pin "2") (pinfunction "2_2") (pintype "passive"))
      (node (ref "JP38") (pin "2") (pinfunction "2_2") (pintype "passive"))
      (node (ref "JP39") (pin "2") (pinfunction "2_2") (pintype "passive"))
      (node (ref "JP40") (pin "2") (pinfunction "2_2") (pintype "passive"))
    )
    (net (code "60") (name "/ROW10") (class "Default")
      (node (ref "B1") (pin "41") (pinfunction "41_41") (pintype "bidirectional"))
      (node (ref "JP33") (pin "2") (pinfunction "2_2") (pintype "passive"))
      (node (ref "JP34") (pin "2") (pinfunction "2_2") (pintype "passive"))
      (node (ref "JP35") (pin "2") (pinfunction "2_2") (pintype "passive"))
      (node (ref "JP36") (pin "2") (pinfunction "2_2") (pintype "passive"))
    )
    (net (code "61") (name "/S0") (class "Default")
      (node (ref "B1") (pin "8") (pinfunction "PWM/8_8") (pintype "bidirectional"))
      (node (ref "IC1") (pin "11") (pinfunction "11_11") (pintype "passive"))
      (node (ref "IC2") (pin "11") (pinfunction "11_11") (pintype "passive"))
      (node (ref "IC3") (pin "11") (pinfunction "11_11") (pintype "passive"))
      (node (ref "IC4") (pin "11") (pinfunction "11_11") (pintype "passive"))
    )
    (net (code "62") (name "/S1") (class "Default")
      (node (ref "B1") (pin "9") (pinfunction "PWM/9_9") (pintype "bidirectional"))
      (node (ref "IC1") (pin "10") (pinfunction "10_10") (pintype "passive"))
      (node (ref "IC2") (pin "10") (pinfunction "10_10") (pintype "passive"))
      (node (ref "IC3") (pin "10") (pinfunction "10_10") (pintype "passive"))
      (node (ref "IC4") (pin "10") (pinfunction "10_10") (pintype "passive"))
    )
    (net (code "63") (name "/S2") (class "Default")
      (node (ref "B1") (pin "10") (pinfunction "PWM/10_10") (pintype "bidirectional"))
      (node (ref "IC1") (pin "9") (pinfunction "9_9") (pintype "passive"))
      (node (ref "IC2") (pin "9") (pinfunction "9_9") (pintype "passive"))
      (node (ref "IC3") (pin "9") (pinfunction "9_9") (pintype "passive"))
      (node (ref "IC4") (pin "9") (pinfunction "9_9") (pintype "passive"))
    )
    (net (code "64") (name "/SHIFT1") (class "Default")
      (node (ref "B1") (pin "6") (pinfunction "PWM/6_6") (pintype "bidirectional"))
      (node (ref "JP77") (pin "2") (pinfunction "2_2") (pintype "passive"))
    )
    (net (code "65") (name "/SHIFT2") (class "Default")
      (node (ref "B1") (pin "7") (pinfunction "PWM/7_7") (pintype "bidirectional"))
      (node (ref "JP78") (pin "2") (pinfunction "2_2") (pintype "passive"))
    )
    (net (code "66") (name "/VIN") (class "Default")
      (node (ref "B1") (pin "VIN") (pinfunction "VIN_VIN") (pintype "power_in"))
    )
    (net (code "67") (name "GND") (class "Default")
      (node (ref "B1") (pin "GND@1") (pinfunction "GND_GND@1") (pintype "power_in"))
      (node (ref "B1") (pin "GND@2") (pinfunction "GND_GND@2") (pintype "power_in"))
      (node (ref "B1") (pin "GND@3") (pinfunction "GND_GND@3") (pintype "power_in"))
      (node (ref "B1") (pin "GND@4") (pinfunction "GND_GND@4") (pintype "power_in"))
      (node (ref "B1") (pin "GND@5") (pinfunction "GND_GND@5") (pintype "power_in"))
      (node (ref "C1") (pin "2") (pinfunction "2_2") (pintype "passive"))
      (node (ref "C2") (pin "2") (pinfunction "2_2") (pintype "passive"))
      (node (ref "C3") (pin "2") (pinfunction "2_2") (pintype "passive"))
      (node (ref "C4") (pin "2") (pinfunction "2_2") (pintype "passive"))
      (node (ref "C5") (pin "2") (pinfunction "2_2") (pintype "passive"))
      (node (ref "C6") (pin "2") (pinfunction "2_2") (pintype "passive"))
      (node (ref "IC1") (pin "6") (pinfunction "6_6") (pintype "passive"))
      (node (ref "IC1") (pin "7") (pinfunction "7_7") (pintype "passive"))
      (node (ref "IC1") (pin "8") (pinfunction "8_8") (pintype "passive"))
      (node (ref "IC2") (pin "6") (pinfunction "6_6") (pintype "passive"))
      (node (ref "IC2") (pin "7") (pinfunction "7_7") (pintype "passive"))
      (node (ref "IC2") (pin "8") (pinfunction "8_8") (pintype "passive"))
      (node (ref "IC3") (pin "6") (pinfunction "6_6") (pintype "passive"))
      (node (ref "IC3") (pin "7") (pinfunction "7_7") (pintype "passive"))
      (node (ref "IC3") (pin "8") (pinfunction "8_8") (pintype "passive"))
      (node (ref "IC4") (pin "6") (pinfunction "6_6") (pintype "passive"))
      (node (ref "IC4") (pin "7") (pinfunction "7_7") (pintype "passive"))
      (node (ref "IC4") (pin "8") (pinfunction "8_8") (pintype "passive"))
      (node (ref "JP73") (pin "2") (pinfunction "2_2") (pintype "passive"))
      (node (ref "JP74") (pin "2") (pinfunction "2_2") (pintype "passive"))
      (node (ref "JP75") (pin "2") (pinfunction "2_2") (pintype "passive"))
      (node (ref "JP76") (pin "2") (pinfunction "2_2") (pintype "passive"))
      (node (ref "JP77") (pin "1") (pinfunction "1_1") (pintype "passive"))
      (node (ref "JP78") (pin "1") (pinfunction "1_1") (pintype "passive"))
      (node (ref "JP79") (pin "1") (pinfunction "1_1") (pintype "passive"))
      (node (ref "R1") (pin "1") (pinfunction "1_1") (pintype "passive"))
      (node (ref "R5") (pin "1") (pinfunction "1_1") (pintype "passive"))
    )
    (net (code "68") (name "Net-(B1-RESET)") (class "Default")
      (node (ref "B1") (pin "RST") (pinfunction "RESET_RST") (pintype "bidirectional"))
      (node (ref "JP79") (pin "2") (pinfunction "2_2") (pintype "passive"))
    )
    (net (code "69") (name "Net-(JP75-Pad3)") (class "Default")
      (node (ref "JP75") (pin "3") (pinfunction "3_3") (pintype "passive"))
      (node (ref "R1") (pin "2") (pinfunction "2_2") (pintype "passive"))
      (node (ref "R2") (pin "1") (pinfunction "1_1") (pintype "passive"))
    )
    (net (code "70") (name "Net-(JP75-Pad4)") (class "Default")
      (node (ref "JP75") (pin "4") (pinfunction "4_4") (pintype "passive"))
      (node (ref "R2") (pin "2") (pinfunction "2_2") (pintype "passive"))
      (node (ref "R3") (pin "1") (pinfunction "1_1") (pintype "passive"))
    )
    (net (code "71") (name "Net-(JP75-Pad5)") (class "Default")
      (node (ref "JP75") (pin "5") (pinfunction "5_5") (pintype "passive"))
      (node (ref "R3") (pin "2") (pinfunction "2_2") (pintype "passive"))
      (node (ref "R4") (pin "1") (pinfunction "1_1") (pintype "passive"))
    )
    (net (code "72") (name "Net-(JP76-Pad3)") (class "Default")
      (node (ref "JP76") (pin "3") (pinfunction "3_3") (pintype "passive"))
      (node (ref "R5") (pin "2") (pinfunction "2_2") (pintype "passive"))
      (node (ref "R6") (pin "1") (pinfunction "1_1") (pintype "passive"))
    )
    (net (code "73") (name "Net-(JP76-Pad4)") (class "Default")
      (node (ref "JP76") (pin "4") (pinfunction "4_4") (pintype "passive"))
      (node (ref "R6") (pin "2") (pinfunction "2_2") (pintype "passive"))
      (node (ref "R7") (pin "1") (pinfunction "1_1") (pintype "passive"))
    )
    (net (code "74") (name "Net-(JP76-Pad5)") (class "Default")
      (node (ref "JP76") (pin "5") (pinfunction "5_5") (pintype "passive"))
      (node (ref "R7") (pin "2") (pinfunction "2_2") (pintype "passive"))
      (node (ref "R8") (pin "1") (pinfunction "1_1") (pintype "passive"))
    )
    (net (code "75") (name "unconnected-(B1-5V-Pad5V@2)") (class "Default")
      (node (ref "B1") (pin "5V@2") (pinfunction "5V_5V@2") (pintype "power_in"))
    )
    (net (code "76") (name "unconnected-(B1-5V-Pad5V@3)") (class "Default")
      (node (ref "B1") (pin "5V@3") (pinfunction "5V_5V@3") (pintype "power_in"))
    )
    (net (code "77") (name "unconnected-(B1-A6{slash}60-PadA6)") (class "Default")
      (node (ref "B1") (pin "A6") (pinfunction "A6/60_A6") (pintype "bidirectional"))
    )
    (net (code "78") (name "unconnected-(B1-A7{slash}61-PadA7)") (class "Default")
      (node (ref "B1") (pin "A7") (pinfunction "A7/61_A7") (pintype "bidirectional"))
    )
    (net (code "79") (name "unconnected-(B1-A8{slash}62-PadA8)") (class "Default")
      (node (ref "B1") (pin "A8") (pinfunction "A8/62_A8") (pintype "bidirectional"))
    )
    (net (code "80") (name "unconnected-(B1-A9{slash}63-PadA9)") (class "Default")
      (node (ref "B1") (pin "A9") (pinfunction "A9/63_A9") (pintype "bidirectional"))
    )
    (net (code "81") (name "unconnected-(B1-A10{slash}64-PadA10)") (class "Default")
      (node (ref "B1") (pin "A10") (pinfunction "A10/64_A10") (pintype "bidirectional"))
    )
    (net (code "82") (name "unconnected-(B1-A11{slash}65-PadA11)") (class "Default")
      (node (ref "B1") (pin "A11") (pinfunction "A11/65_A11") (pintype "bidirectional"))
    )
    (net (code "83") (name "unconnected-(B1-A12{slash}66-PadA12)") (class "Default")
      (node (ref "B1") (pin "A12") (pinfunction "A12/66_A12") (pintype "bidirectional"))
    )
    (net (code "84") (name "unconnected-(B1-A13{slash}67-PadA13)") (class "Default")
      (node (ref "B1") (pin "A13") (pinfunction "A13/67_A13") (pintype "bidirectional"))
    )
    (net (code "85") (name "unconnected-(B1-A14{slash}68-PadA14)") (class "Default")
      (node (ref "B1") (pin "A14") (pinfunction "A14/68_A14") (pintype "bidirectional"))
    )
    (net (code "86") (name "unconnected-(B1-A15{slash}69-PadA15)") (class "Default")
      (node (ref "B1") (pin "A15") (pinfunction "A15/69_A15") (pintype "bidirectional"))
    )
    (net (code "87") (name "unconnected-(B1-MISO{slash}50-Pad50)") (class "Default")
      (node (ref "B1") (pin "50") (pinfunction "MISO/50_50") (pintype "bidirectional"))
    )
    (net (code "88") (name "unconnected-(B1-MOSI{slash}51-Pad51)") (class "Default")
      (node (ref "B1") (pin "51") (pinfunction "MOSI/51_51") (pintype "bidirectional"))
    )
    (net (code "89") (name "unconnected-(B1-PWM{slash}2-Pad2)") (class "Default")
      (node (ref "B1") (pin "2") (pinfunction "PWM/2_2") (pintype "bidirectional"))
    )
    (net (code "90") (name "unconnected-(B1-PWM{slash}3-Pad3)") (class "Default")
      (node (ref "B1") (pin "3") (pinfunction "PWM/3_3") (pintype "bidirectional"))
    )
    (net (code "91") (name "unconnected-(B1-PWM{slash}4-Pad4)") (class "Default")
      (node (ref "B1") (pin "4") (pinfunction "PWM/4_4") (pintype "bidirectional"))
    )
    (net (code "92") (name "unconnected-(B1-PWM{slash}5-Pad5)") (class "Default")
      (node (ref "B1") (pin "5") (pinfunction "PWM/5_5") (pintype "bidirectional"))
    )
    (net (code "93") (name "unconnected-(B1-PWM{slash}11-Pad11)") (class "Default")
      (node (ref "B1") (pin "11") (pinfunction "PWM/11_11") (pintype "bidirectional"))
    )
    (net (code "94") (name "unconnected-(B1-PWM{slash}12-Pad12)") (class "Default")
      (node (ref "B1") (pin "12") (pinfunction "PWM/12_12") (pintype "bidirectional"))
    )
    (net (code "95") (name "unconnected-(B1-PWM{slash}13-Pad13)") (class "Default")
      (node (ref "B1") (pin "13") (pinfunction "PWM/13_13") (pintype "bidirectional"))
    )
    (net (code "96") (name "unconnected-(B1-PWM{slash}44-Pad44)") (class "Default")
      (node (ref "B1") (pin "44") (pinfunction "PWM/44_44") (pintype "bidirectional"))
    )
    (net (code "97") (name "unconnected-(B1-PWM{slash}45-Pad45)") (class "Default")
      (node (ref "B1") (pin "45") (pinfunction "PWM/45_45") (pintype "bidirectional"))
    )
    (net (code "98") (name "unconnected-(B1-PWM{slash}46-Pad46)") (class "Default")
      (node (ref "B1") (pin "46") (pinfunction "PWM/46_46") (pintype "bidirectional"))
    )
    (net (code "99") (name "unconnected-(B1-Pad30)") (class "Default")
      (node (ref "B1") (pin "30") (pinfunction "30_30") (pintype "bidirectional"))
    )
    (net (code "100") (name "unconnected-(B1-Pad32)") (class "Default")
      (node (ref "B1") (pin "32") (pinfunction "32_32") (pintype "bidirectional"))
    )
    (net (code "101") (name "unconnected-(B1-Pad34)") (class "Default")
      (node (ref "B1") (pin "34") (pinfunction "34_34") (pintype "bidirectional"))
    )
    (net (code "102") (name "unconnected-(B1-Pad36)") (class "Default")
      (node (ref "B1") (pin "36") (pinfunction "36_36") (pintype "bidirectional"))
    )
    (net (code "103") (name "unconnected-(B1-Pad38)") (class "Default")
      (node (ref "B1") (pin "38") (pinfunction "38_38") (pintype "bidirectional"))
    )
    (net (code "104") (name "unconnected-(B1-Pad40)") (class "Default")
      (node (ref "B1") (pin "40") (pinfunction "40_40") (pintype "bidirectional"))
    )
    (net (code "105") (name "unconnected-(B1-Pad42)") (class "Default")
      (node (ref "B1") (pin "42") (pinfunction "42_42") (pintype "bidirectional"))
    )
    (net (code "106") (name "unconnected-(B1-Pad43)") (class "Default")
      (node (ref "B1") (pin "43") (pinfunction "43_43") (pintype "bidirectional"))
    )
    (net (code "107") (name "unconnected-(B1-Pad47)") (class "Default")
      (node (ref "B1") (pin "47") (pinfunction "47_47") (pintype "bidirectional"))
    )
    (net (code "108") (name "unconnected-(B1-Pad48)") (class "Default")
      (node (ref "B1") (pin "48") (pinfunction "48_48") (pintype "bidirectional"))
    )
    (net (code "109") (name "unconnected-(B1-Pad49)") (class "Default")
      (node (ref "B1") (pin "49") (pinfunction "49_49") (pintype "bidirectional"))
    )
    (net (code "110") (name "unconnected-(B1-PadSCL)") (class "Default")
      (node (ref "B1") (pin "SCL") (pinfunction "SCL_SCL") (pintype "bidirectional"))
    )
    (net (code "111") (name "unconnected-(B1-PadSDA)") (class "Default")
      (node (ref "B1") (pin "SDA") (pinfunction "SDA_SDA") (pintype "bidirectional"))
    )
    (net (code "112") (name "unconnected-(B1-RX2{slash}17-Pad17)") (class "Default")
      (node (ref "B1") (pin "17") (pinfunction "RX2/17_17") (pintype "bidirectional"))
    )
    (net (code "113") (name "unconnected-(B1-RX3{slash}15-Pad15)") (class "Default")
      (node (ref "B1") (pin "15") (pinfunction "RX3/15_15") (pintype "bidirectional"))
    )
    (net (code "114") (name "unconnected-(B1-RX{slash}0-Pad0)") (class "Default")
      (node (ref "B1") (pin "0") (pinfunction "RX/0_0") (pintype "bidirectional"))
    )
    (net (code "115") (name "unconnected-(B1-SCK{slash}52-Pad52)") (class "Default")
      (node (ref "B1") (pin "52") (pinfunction "SCK/52_52") (pintype "bidirectional"))
    )
    (net (code "116") (name "unconnected-(B1-SS{slash}53-Pad53)") (class "Default")
      (node (ref "B1") (pin "53") (pinfunction "SS/53_53") (pintype "bidirectional"))
    )
    (net (code "117") (name "unconnected-(B1-TX2{slash}16-Pad16)") (class "Default")
      (node (ref "B1") (pin "16") (pinfunction "TX2/16_16") (pintype "bidirectional"))
    )
    (net (code "118") (name "unconnected-(B1-TX3{slash}14-Pad14)") (class "Default")
      (node (ref "B1") (pin "14") (pinfunction "TX3/14_14") (pintype "bidirectional"))
    )
    (net (code "119") (name "unconnected-(B1-TX{slash}1-Pad1)") (class "Default")
      (node (ref "B1") (pin "1") (pinfunction "TX/1_1") (pintype "bidirectional"))
    )
  )
)
